# Stack_Address_Register.net
KiCad netlist of a schematic drawn in Altium Designer
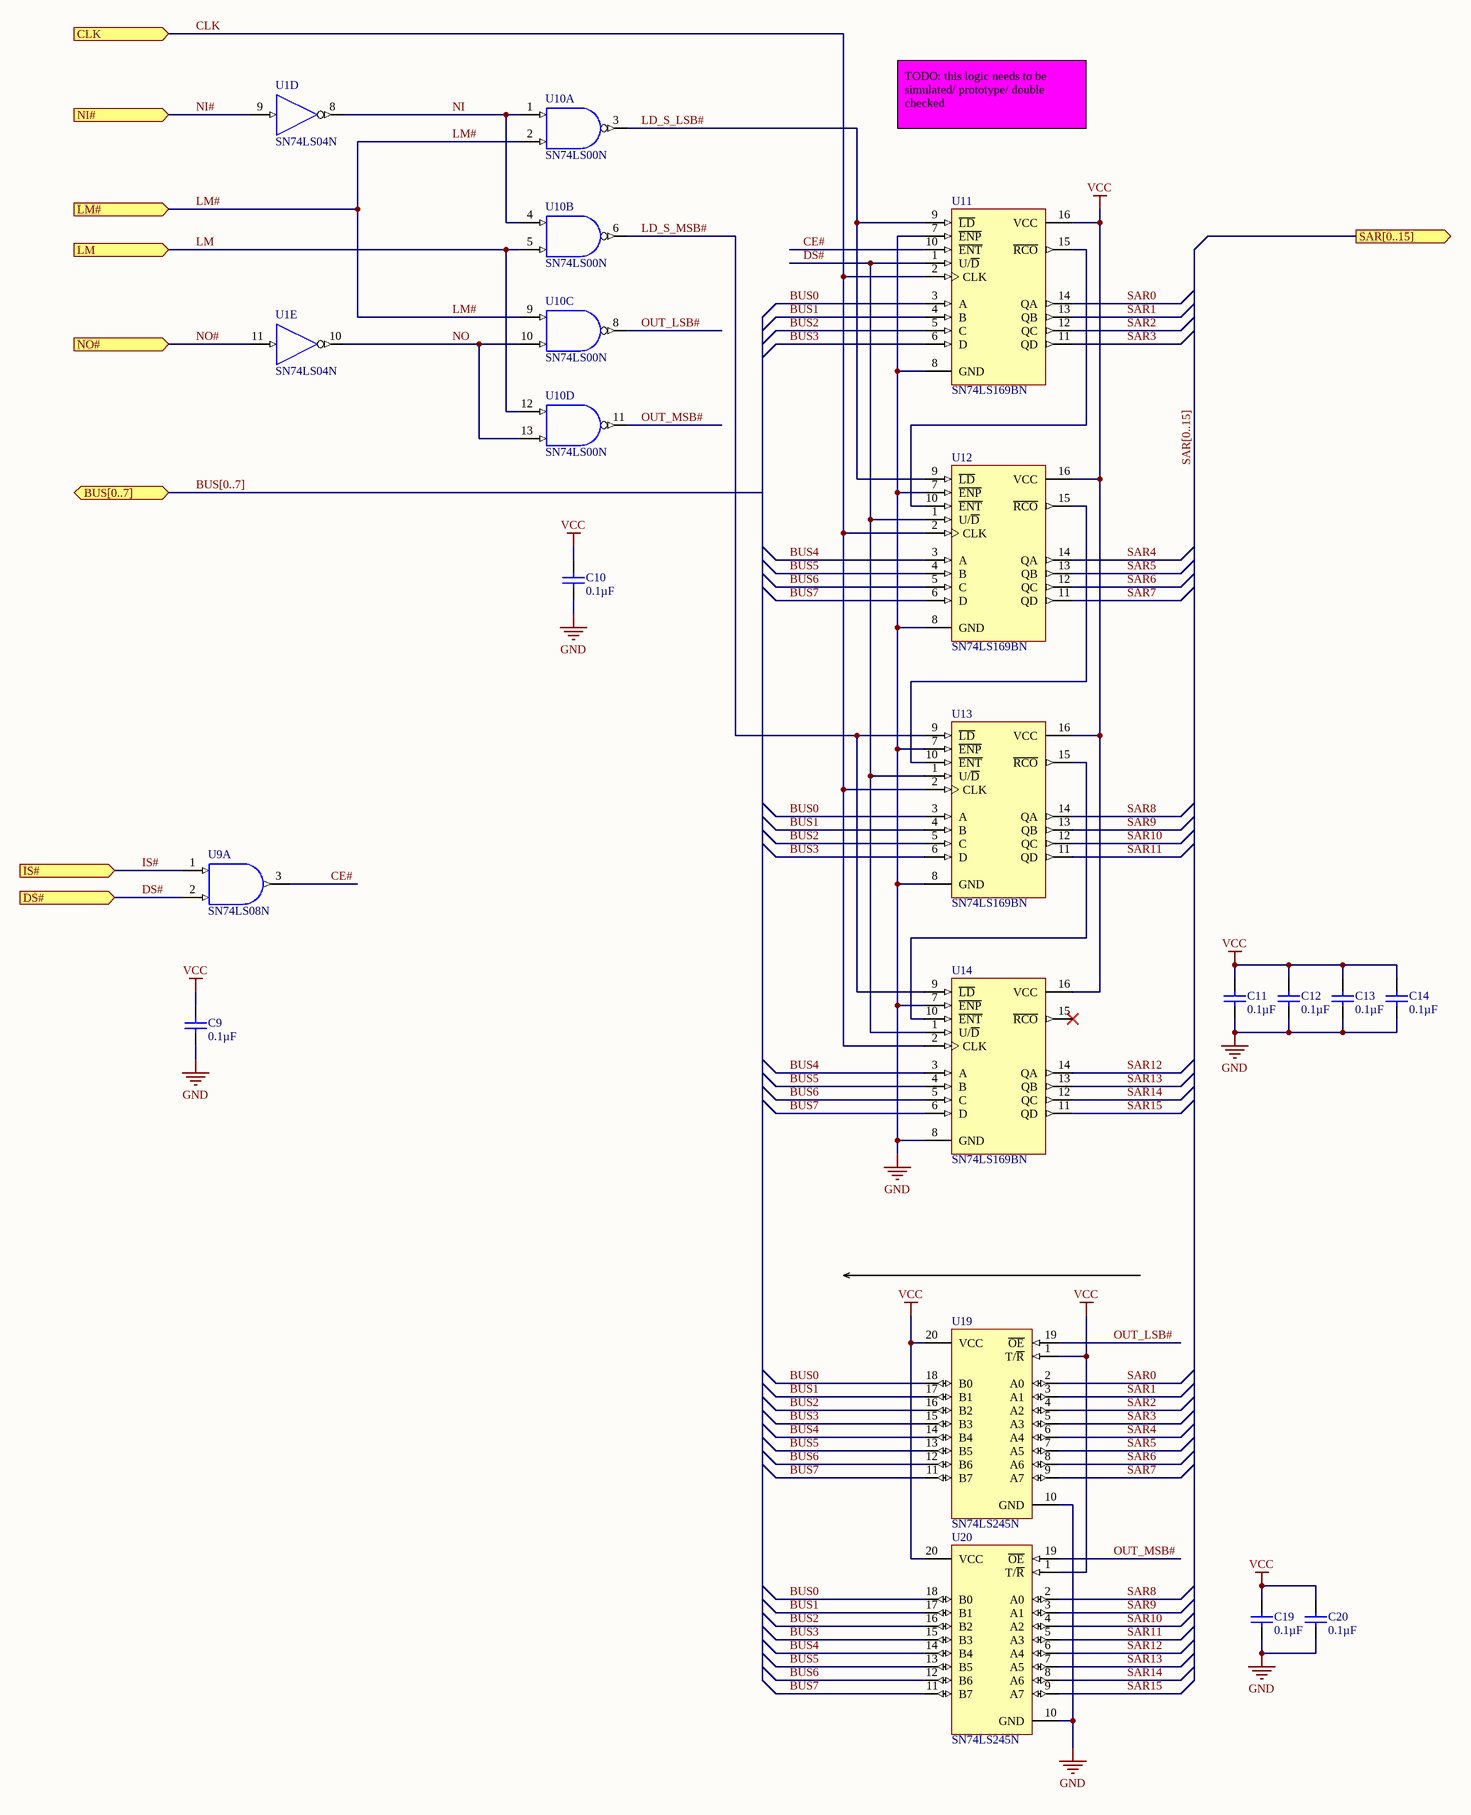
[diagram p0: Stack Address Register.SchDoc]

(export (version "E")
  (design (tool "Eeschema 10.0.6"))
  (components
    (comp (ref "C9")
      (value "K104K15X7RF5TL2")
      (footprint "VISH-K104K15X7RF5TL2")
      (description "Ceramic Capacitor, 100 nF, +/- 10%, 50 V, -55 to 125 degC, 2-Pin THD, RoHS, Tape and Reel")
      (fields
        (field (name "MANUFACTURER") "Vishay")
        (field (name "TOLERANCE") "±10%")
        (field (name "CAPACITANCE") "0.1µF")
      )
      (libsource (lib "Altium Content Vault") (part "CAP-NP-2"))
    )
    (comp (ref "C10")
      (value "K104K15X7RF5TL2")
      (footprint "VISH-K104K15X7RF5TL2")
      (description "Ceramic Capacitor, 100 nF, +/- 10%, 50 V, -55 to 125 degC, 2-Pin THD, RoHS, Tape and Reel")
      (fields
        (field (name "MANUFACTURER") "Vishay")
        (field (name "TOLERANCE") "±10%")
        (field (name "CAPACITANCE") "0.1µF")
      )
      (libsource (lib "Altium Content Vault") (part "CAP-NP-2"))
    )
    (comp (ref "C11")
      (value "K104K15X7RF5TL2")
      (footprint "VISH-K104K15X7RF5TL2")
      (description "Ceramic Capacitor, 100 nF, +/- 10%, 50 V, -55 to 125 degC, 2-Pin THD, RoHS, Tape and Reel")
      (fields
        (field (name "MANUFACTURER") "Vishay")
        (field (name "TOLERANCE") "±10%")
        (field (name "CAPACITANCE") "0.1µF")
      )
      (libsource (lib "Altium Content Vault") (part "CAP-NP-2"))
    )
    (comp (ref "C12")
      (value "K104K15X7RF5TL2")
      (footprint "VISH-K104K15X7RF5TL2")
      (description "Ceramic Capacitor, 100 nF, +/- 10%, 50 V, -55 to 125 degC, 2-Pin THD, RoHS, Tape and Reel")
      (fields
        (field (name "MANUFACTURER") "Vishay")
        (field (name "TOLERANCE") "±10%")
        (field (name "CAPACITANCE") "0.1µF")
      )
      (libsource (lib "Altium Content Vault") (part "CAP-NP-2"))
    )
    (comp (ref "C13")
      (value "K104K15X7RF5TL2")
      (footprint "VISH-K104K15X7RF5TL2")
      (description "Ceramic Capacitor, 100 nF, +/- 10%, 50 V, -55 to 125 degC, 2-Pin THD, RoHS, Tape and Reel")
      (fields
        (field (name "MANUFACTURER") "Vishay")
        (field (name "TOLERANCE") "±10%")
        (field (name "CAPACITANCE") "0.1µF")
      )
      (libsource (lib "Altium Content Vault") (part "CAP-NP-2"))
    )
    (comp (ref "C14")
      (value "K104K15X7RF5TL2")
      (footprint "VISH-K104K15X7RF5TL2")
      (description "Ceramic Capacitor, 100 nF, +/- 10%, 50 V, -55 to 125 degC, 2-Pin THD, RoHS, Tape and Reel")
      (fields
        (field (name "MANUFACTURER") "Vishay")
        (field (name "TOLERANCE") "±10%")
        (field (name "CAPACITANCE") "0.1µF")
      )
      (libsource (lib "Altium Content Vault") (part "CAP-NP-2"))
    )
    (comp (ref "C19")
      (value "K104K15X7RF5TL2")
      (footprint "VISH-K104K15X7RF5TL2")
      (description "Ceramic Capacitor, 100 nF, +/- 10%, 50 V, -55 to 125 degC, 2-Pin THD, RoHS, Tape and Reel")
      (fields
        (field (name "MANUFACTURER") "Vishay")
        (field (name "TOLERANCE") "±10%")
        (field (name "CAPACITANCE") "0.1µF")
      )
      (libsource (lib "Altium Content Vault") (part "CAP-NP-2"))
    )
    (comp (ref "C20")
      (value "K104K15X7RF5TL2")
      (footprint "VISH-K104K15X7RF5TL2")
      (description "Ceramic Capacitor, 100 nF, +/- 10%, 50 V, -55 to 125 degC, 2-Pin THD, RoHS, Tape and Reel")
      (fields
        (field (name "MANUFACTURER") "Vishay")
        (field (name "TOLERANCE") "±10%")
        (field (name "CAPACITANCE") "0.1µF")
      )
      (libsource (lib "Altium Content Vault") (part "CAP-NP-2"))
    )
    (comp (ref "U1")
      (value "SN74LS04N")
      (footprint "N014")
      (description "Hex Inverter")
      (fields (field (name "PUBLISHER") "Altium Limited"))
      (libsource (lib "TI Logic Gate 2") (part "SN74LS04N"))
    )
    (comp (ref "U9")
      (value "SN74LS08N")
      (footprint "N014")
      (description "Quadruple 2-Input Positive-AND Gate")
      (fields (field (name "PUBLISHER") "Altium Limited"))
      (libsource (lib "TI Logic Gate 2") (part "SN74LS08N"))
    )
    (comp (ref "U10")
      (value "SN74LS00N")
      (footprint "N014")
      (description "Quadruple 2-Input Positive-NAND Gate")
      (fields (field (name "PUBLISHER") "Altium Limited"))
      (libsource (lib "TI Logic Gate 2") (part "SN74LS00N"))
    )
    (comp (ref "U11")
      (value "SN74LS169BN")
      (footprint "N016")
      (description "Synchronous 4-Bit Up/Down Binary Counter")
      (fields (field (name "PUBLISHER") "Altium Limited"))
      (libsource (lib "TI Logic Counter") (part "SN74LS169BN"))
    )
    (comp (ref "U12")
      (value "SN74LS169BN")
      (footprint "N016")
      (description "Synchronous 4-Bit Up/Down Binary Counter")
      (fields (field (name "PUBLISHER") "Altium Limited"))
      (libsource (lib "TI Logic Counter") (part "SN74LS169BN"))
    )
    (comp (ref "U13")
      (value "SN74LS169BN")
      (footprint "N016")
      (description "Synchronous 4-Bit Up/Down Binary Counter")
      (fields (field (name "PUBLISHER") "Altium Limited"))
      (libsource (lib "TI Logic Counter") (part "SN74LS169BN"))
    )
    (comp (ref "U14")
      (value "SN74LS169BN")
      (footprint "N016")
      (description "Synchronous 4-Bit Up/Down Binary Counter")
      (fields (field (name "PUBLISHER") "Altium Limited"))
      (libsource (lib "TI Logic Counter") (part "SN74LS169BN"))
    )
    (comp (ref "U19")
      (value "SN74LS245N")
      (footprint "N020")
      (description "Octal Bus Transceiver with 3-State Outputs")
      (fields (field (name "PUBLISHER") "Altium Limited"))
      (libsource (lib "TI Interface 8-Bit Line Transceiver") (part "SN74LS245N"))
    )
    (comp (ref "U20")
      (value "SN74LS245N")
      (footprint "N020")
      (description "Octal Bus Transceiver with 3-State Outputs")
      (fields (field (name "PUBLISHER") "Altium Limited"))
      (libsource (lib "TI Interface 8-Bit Line Transceiver") (part "SN74LS245N"))
    )
  )
  (nets
    (net (code "1") (name "/BUS0") (class "Default")
      (node (ref "U11") (pin "3") (pinfunction "A_3") (pintype "input"))
      (node (ref "U13") (pin "3") (pinfunction "A_3") (pintype "input"))
      (node (ref "U19") (pin "18") (pinfunction "B0_18") (pintype "bidirectional"))
      (node (ref "U20") (pin "18") (pinfunction "B0_18") (pintype "bidirectional"))
    )
    (net (code "2") (name "/BUS1") (class "Default")
      (node (ref "U11") (pin "4") (pinfunction "B_4") (pintype "input"))
      (node (ref "U13") (pin "4") (pinfunction "B_4") (pintype "input"))
      (node (ref "U19") (pin "17") (pinfunction "B1_17") (pintype "bidirectional"))
      (node (ref "U20") (pin "17") (pinfunction "B1_17") (pintype "bidirectional"))
    )
    (net (code "3") (name "/BUS2") (class "Default")
      (node (ref "U11") (pin "5") (pinfunction "C_5") (pintype "input"))
      (node (ref "U13") (pin "5") (pinfunction "C_5") (pintype "input"))
      (node (ref "U19") (pin "16") (pinfunction "B2_16") (pintype "bidirectional"))
      (node (ref "U20") (pin "16") (pinfunction "B2_16") (pintype "bidirectional"))
    )
    (net (code "4") (name "/BUS3") (class "Default")
      (node (ref "U11") (pin "6") (pinfunction "D_6") (pintype "input"))
      (node (ref "U13") (pin "6") (pinfunction "D_6") (pintype "input"))
      (node (ref "U19") (pin "15") (pinfunction "B3_15") (pintype "bidirectional"))
      (node (ref "U20") (pin "15") (pinfunction "B3_15") (pintype "bidirectional"))
    )
    (net (code "5") (name "/BUS4") (class "Default")
      (node (ref "U12") (pin "3") (pinfunction "A_3") (pintype "input"))
      (node (ref "U14") (pin "3") (pinfunction "A_3") (pintype "input"))
      (node (ref "U19") (pin "14") (pinfunction "B4_14") (pintype "bidirectional"))
      (node (ref "U20") (pin "14") (pinfunction "B4_14") (pintype "bidirectional"))
    )
    (net (code "6") (name "/BUS5") (class "Default")
      (node (ref "U12") (pin "4") (pinfunction "B_4") (pintype "input"))
      (node (ref "U14") (pin "4") (pinfunction "B_4") (pintype "input"))
      (node (ref "U19") (pin "13") (pinfunction "B5_13") (pintype "bidirectional"))
      (node (ref "U20") (pin "13") (pinfunction "B5_13") (pintype "bidirectional"))
    )
    (net (code "7") (name "/BUS6") (class "Default")
      (node (ref "U12") (pin "5") (pinfunction "C_5") (pintype "input"))
      (node (ref "U14") (pin "5") (pinfunction "C_5") (pintype "input"))
      (node (ref "U19") (pin "12") (pinfunction "B6_12") (pintype "bidirectional"))
      (node (ref "U20") (pin "12") (pinfunction "B6_12") (pintype "bidirectional"))
    )
    (net (code "8") (name "/BUS7") (class "Default")
      (node (ref "U12") (pin "6") (pinfunction "D_6") (pintype "input"))
      (node (ref "U14") (pin "6") (pinfunction "D_6") (pintype "input"))
      (node (ref "U19") (pin "11") (pinfunction "B7_11") (pintype "bidirectional"))
      (node (ref "U20") (pin "11") (pinfunction "B7_11") (pintype "bidirectional"))
    )
    (net (code "10") (name "/CE#") (class "Default")
      (node (ref "U11") (pin "10") (pinfunction "~{ENT}_10") (pintype "input"))
      (node (ref "U9") (pin "3") (pinfunction "Y_3") (pintype "output"))
    )
    (net (code "11") (name "/CLK") (class "Default")
      (node (ref "U11") (pin "2") (pinfunction "CLK_2") (pintype "input"))
      (node (ref "U12") (pin "2") (pinfunction "CLK_2") (pintype "input"))
      (node (ref "U13") (pin "2") (pinfunction "CLK_2") (pintype "input"))
      (node (ref "U14") (pin "2") (pinfunction "CLK_2") (pintype "input"))
    )
    (net (code "12") (name "/DS#") (class "Default")
      (node (ref "U11") (pin "1") (pinfunction "U/~{D}_1") (pintype "input"))
      (node (ref "U12") (pin "1") (pinfunction "U/~{D}_1") (pintype "input"))
      (node (ref "U13") (pin "1") (pinfunction "U/~{D}_1") (pintype "input"))
      (node (ref "U14") (pin "1") (pinfunction "U/~{D}_1") (pintype "input"))
      (node (ref "U9") (pin "2") (pinfunction "B_2") (pintype "input"))
    )
    (net (code "13") (name "/IS#") (class "Default")
      (node (ref "U9") (pin "1") (pinfunction "A_1") (pintype "input"))
    )
    (net (code "14") (name "/LD_S_LSB#") (class "Default")
      (node (ref "U10") (pin "3") (pinfunction "Y_3") (pintype "output"))
      (node (ref "U11") (pin "9") (pinfunction "~{LD}_9") (pintype "input"))
      (node (ref "U12") (pin "9") (pinfunction "~{LD}_9") (pintype "input"))
    )
    (net (code "15") (name "/LD_S_MSB#") (class "Default")
      (node (ref "U10") (pin "6") (pinfunction "Y_6") (pintype "output"))
      (node (ref "U13") (pin "9") (pinfunction "~{LD}_9") (pintype "input"))
      (node (ref "U14") (pin "9") (pinfunction "~{LD}_9") (pintype "input"))
    )
    (net (code "16") (name "/LM") (class "Default")
      (node (ref "U10") (pin "12") (pinfunction "A_12") (pintype "input"))
      (node (ref "U10") (pin "5") (pinfunction "B_5") (pintype "input"))
    )
    (net (code "17") (name "/LM#") (class "Default")
      (node (ref "U10") (pin "2") (pinfunction "B_2") (pintype "input"))
      (node (ref "U10") (pin "9") (pinfunction "A_9") (pintype "input"))
    )
    (net (code "18") (name "/NI") (class "Default")
      (node (ref "U1") (pin "8") (pinfunction "Y_8") (pintype "output"))
      (node (ref "U10") (pin "1") (pinfunction "A_1") (pintype "input"))
      (node (ref "U10") (pin "4") (pinfunction "A_4") (pintype "input"))
    )
    (net (code "19") (name "/NI#") (class "Default")
      (node (ref "U1") (pin "9") (pinfunction "A_9") (pintype "input"))
    )
    (net (code "20") (name "/NO") (class "Default")
      (node (ref "U1") (pin "10") (pinfunction "Y_10") (pintype "output"))
      (node (ref "U10") (pin "10") (pinfunction "B_10") (pintype "input"))
      (node (ref "U10") (pin "13") (pinfunction "B_13") (pintype "input"))
    )
    (net (code "21") (name "/NO#") (class "Default")
      (node (ref "U1") (pin "11") (pinfunction "A_11") (pintype "input"))
    )
    (net (code "22") (name "/OUT_LSB#") (class "Default")
      (node (ref "U10") (pin "8") (pinfunction "Y_8") (pintype "output"))
      (node (ref "U19") (pin "19") (pinfunction "~{OE}_19") (pintype "input"))
    )
    (net (code "23") (name "/OUT_MSB#") (class "Default")
      (node (ref "U10") (pin "11") (pinfunction "Y_11") (pintype "output"))
      (node (ref "U20") (pin "19") (pinfunction "~{OE}_19") (pintype "input"))
    )
    (net (code "24") (name "/SAR0") (class "Default")
      (node (ref "U11") (pin "14") (pinfunction "QA_14") (pintype "output"))
      (node (ref "U19") (pin "2") (pinfunction "A0_2") (pintype "bidirectional"))
    )
    (net (code "25") (name "/SAR1") (class "Default")
      (node (ref "U11") (pin "13") (pinfunction "QB_13") (pintype "output"))
      (node (ref "U19") (pin "3") (pinfunction "A1_3") (pintype "bidirectional"))
    )
    (net (code "26") (name "/SAR2") (class "Default")
      (node (ref "U11") (pin "12") (pinfunction "QC_12") (pintype "output"))
      (node (ref "U19") (pin "4") (pinfunction "A2_4") (pintype "bidirectional"))
    )
    (net (code "27") (name "/SAR3") (class "Default")
      (node (ref "U11") (pin "11") (pinfunction "QD_11") (pintype "output"))
      (node (ref "U19") (pin "5") (pinfunction "A3_5") (pintype "bidirectional"))
    )
    (net (code "28") (name "/SAR4") (class "Default")
      (node (ref "U12") (pin "14") (pinfunction "QA_14") (pintype "output"))
      (node (ref "U19") (pin "6") (pinfunction "A4_6") (pintype "bidirectional"))
    )
    (net (code "29") (name "/SAR5") (class "Default")
      (node (ref "U12") (pin "13") (pinfunction "QB_13") (pintype "output"))
      (node (ref "U19") (pin "7") (pinfunction "A5_7") (pintype "bidirectional"))
    )
    (net (code "30") (name "/SAR6") (class "Default")
      (node (ref "U12") (pin "12") (pinfunction "QC_12") (pintype "output"))
      (node (ref "U19") (pin "8") (pinfunction "A6_8") (pintype "bidirectional"))
    )
    (net (code "31") (name "/SAR7") (class "Default")
      (node (ref "U12") (pin "11") (pinfunction "QD_11") (pintype "output"))
      (node (ref "U19") (pin "9") (pinfunction "A7_9") (pintype "bidirectional"))
    )
    (net (code "32") (name "/SAR8") (class "Default")
      (node (ref "U13") (pin "14") (pinfunction "QA_14") (pintype "output"))
      (node (ref "U20") (pin "2") (pinfunction "A0_2") (pintype "bidirectional"))
    )
    (net (code "33") (name "/SAR9") (class "Default")
      (node (ref "U13") (pin "13") (pinfunction "QB_13") (pintype "output"))
      (node (ref "U20") (pin "3") (pinfunction "A1_3") (pintype "bidirectional"))
    )
    (net (code "34") (name "/SAR10") (class "Default")
      (node (ref "U13") (pin "12") (pinfunction "QC_12") (pintype "output"))
      (node (ref "U20") (pin "4") (pinfunction "A2_4") (pintype "bidirectional"))
    )
    (net (code "35") (name "/SAR11") (class "Default")
      (node (ref "U13") (pin "11") (pinfunction "QD_11") (pintype "output"))
      (node (ref "U20") (pin "5") (pinfunction "A3_5") (pintype "bidirectional"))
    )
    (net (code "36") (name "/SAR12") (class "Default")
      (node (ref "U14") (pin "14") (pinfunction "QA_14") (pintype "output"))
      (node (ref "U20") (pin "6") (pinfunction "A4_6") (pintype "bidirectional"))
    )
    (net (code "37") (name "/SAR13") (class "Default")
      (node (ref "U14") (pin "13") (pinfunction "QB_13") (pintype "output"))
      (node (ref "U20") (pin "7") (pinfunction "A5_7") (pintype "bidirectional"))
    )
    (net (code "38") (name "/SAR14") (class "Default")
      (node (ref "U14") (pin "12") (pinfunction "QC_12") (pintype "output"))
      (node (ref "U20") (pin "8") (pinfunction "A6_8") (pintype "bidirectional"))
    )
    (net (code "39") (name "/SAR15") (class "Default")
      (node (ref "U14") (pin "11") (pinfunction "QD_11") (pintype "output"))
      (node (ref "U20") (pin "9") (pinfunction "A7_9") (pintype "bidirectional"))
    )
    (net (code "41") (name "GND") (class "Default")
      (node (ref "C10") (pin "2") (pinfunction "2_2") (pintype "passive"))
      (node (ref "C11") (pin "2") (pinfunction "2_2") (pintype "passive"))
      (node (ref "C12") (pin "2") (pinfunction "2_2") (pintype "passive"))
      (node (ref "C13") (pin "2") (pinfunction "2_2") (pintype "passive"))
      (node (ref "C14") (pin "2") (pinfunction "2_2") (pintype "passive"))
      (node (ref "C19") (pin "2") (pinfunction "2_2") (pintype "passive"))
      (node (ref "C20") (pin "2") (pinfunction "2_2") (pintype "passive"))
      (node (ref "C9") (pin "2") (pinfunction "2_2") (pintype "passive"))
      (node (ref "U1") (pin "7") (pinfunction "GND_7") (pintype "power_in"))
      (node (ref "U10") (pin "7") (pinfunction "GND_7") (pintype "power_in"))
      (node (ref "U11") (pin "7") (pinfunction "~{ENP}_7") (pintype "input"))
      (node (ref "U11") (pin "8") (pinfunction "GND_8") (pintype "power_in"))
      (node (ref "U12") (pin "7") (pinfunction "~{ENP}_7") (pintype "input"))
      (node (ref "U12") (pin "8") (pinfunction "GND_8") (pintype "power_in"))
      (node (ref "U13") (pin "7") (pinfunction "~{ENP}_7") (pintype "input"))
      (node (ref "U13") (pin "8") (pinfunction "GND_8") (pintype "power_in"))
      (node (ref "U14") (pin "7") (pinfunction "~{ENP}_7") (pintype "input"))
      (node (ref "U14") (pin "8") (pinfunction "GND_8") (pintype "power_in"))
      (node (ref "U19") (pin "10") (pinfunction "GND_10") (pintype "power_in"))
      (node (ref "U20") (pin "10") (pinfunction "GND_10") (pintype "power_in"))
      (node (ref "U9") (pin "7") (pinfunction "GND_7") (pintype "power_in"))
    )
    (net (code "42") (name "Net-(U11-~{RCO})") (class "Default")
      (node (ref "U11") (pin "15") (pinfunction "~{RCO}_15") (pintype "output"))
      (node (ref "U12") (pin "10") (pinfunction "~{ENT}_10") (pintype "input"))
    )
    (net (code "43") (name "Net-(U12-~{RCO})") (class "Default")
      (node (ref "U12") (pin "15") (pinfunction "~{RCO}_15") (pintype "output"))
      (node (ref "U13") (pin "10") (pinfunction "~{ENT}_10") (pintype "input"))
    )
    (net (code "44") (name "Net-(U13-~{RCO})") (class "Default")
      (node (ref "U13") (pin "15") (pinfunction "~{RCO}_15") (pintype "output"))
      (node (ref "U14") (pin "10") (pinfunction "~{ENT}_10") (pintype "input"))
    )
    (net (code "45") (name "VCC") (class "Default")
      (node (ref "C10") (pin "1") (pinfunction "1_1") (pintype "passive"))
      (node (ref "C11") (pin "1") (pinfunction "1_1") (pintype "passive"))
      (node (ref "C12") (pin "1") (pinfunction "1_1") (pintype "passive"))
      (node (ref "C13") (pin "1") (pinfunction "1_1") (pintype "passive"))
      (node (ref "C14") (pin "1") (pinfunction "1_1") (pintype "passive"))
      (node (ref "C19") (pin "1") (pinfunction "1_1") (pintype "passive"))
      (node (ref "C20") (pin "1") (pinfunction "1_1") (pintype "passive"))
      (node (ref "C9") (pin "1") (pinfunction "1_1") (pintype "passive"))
      (node (ref "U1") (pin "14") (pinfunction "VCC_14") (pintype "power_in"))
      (node (ref "U10") (pin "14") (pinfunction "VCC_14") (pintype "power_in"))
      (node (ref "U11") (pin "16") (pinfunction "VCC_16") (pintype "power_in"))
      (node (ref "U12") (pin "16") (pinfunction "VCC_16") (pintype "power_in"))
      (node (ref "U13") (pin "16") (pinfunction "VCC_16") (pintype "power_in"))
      (node (ref "U14") (pin "16") (pinfunction "VCC_16") (pintype "power_in"))
      (node (ref "U19") (pin "1") (pinfunction "T/~{R}_1") (pintype "input"))
      (node (ref "U19") (pin "20") (pinfunction "VCC_20") (pintype "power_in"))
      (node (ref "U20") (pin "1") (pinfunction "T/~{R}_1") (pintype "input"))
      (node (ref "U20") (pin "20") (pinfunction "VCC_20") (pintype "power_in"))
      (node (ref "U9") (pin "14") (pinfunction "VCC_14") (pintype "power_in"))
    )
    (net (code "46") (name "unconnected-(U14-~{RCO}-Pad15)") (class "Default")
      (node (ref "U14") (pin "15") (pinfunction "~{RCO}_15") (pintype "output+no_connect"))
    )
  )
)
